# Atmega328p_Shift_Register.net
KiCad netlist of a schematic drawn in EasyEDA Pro
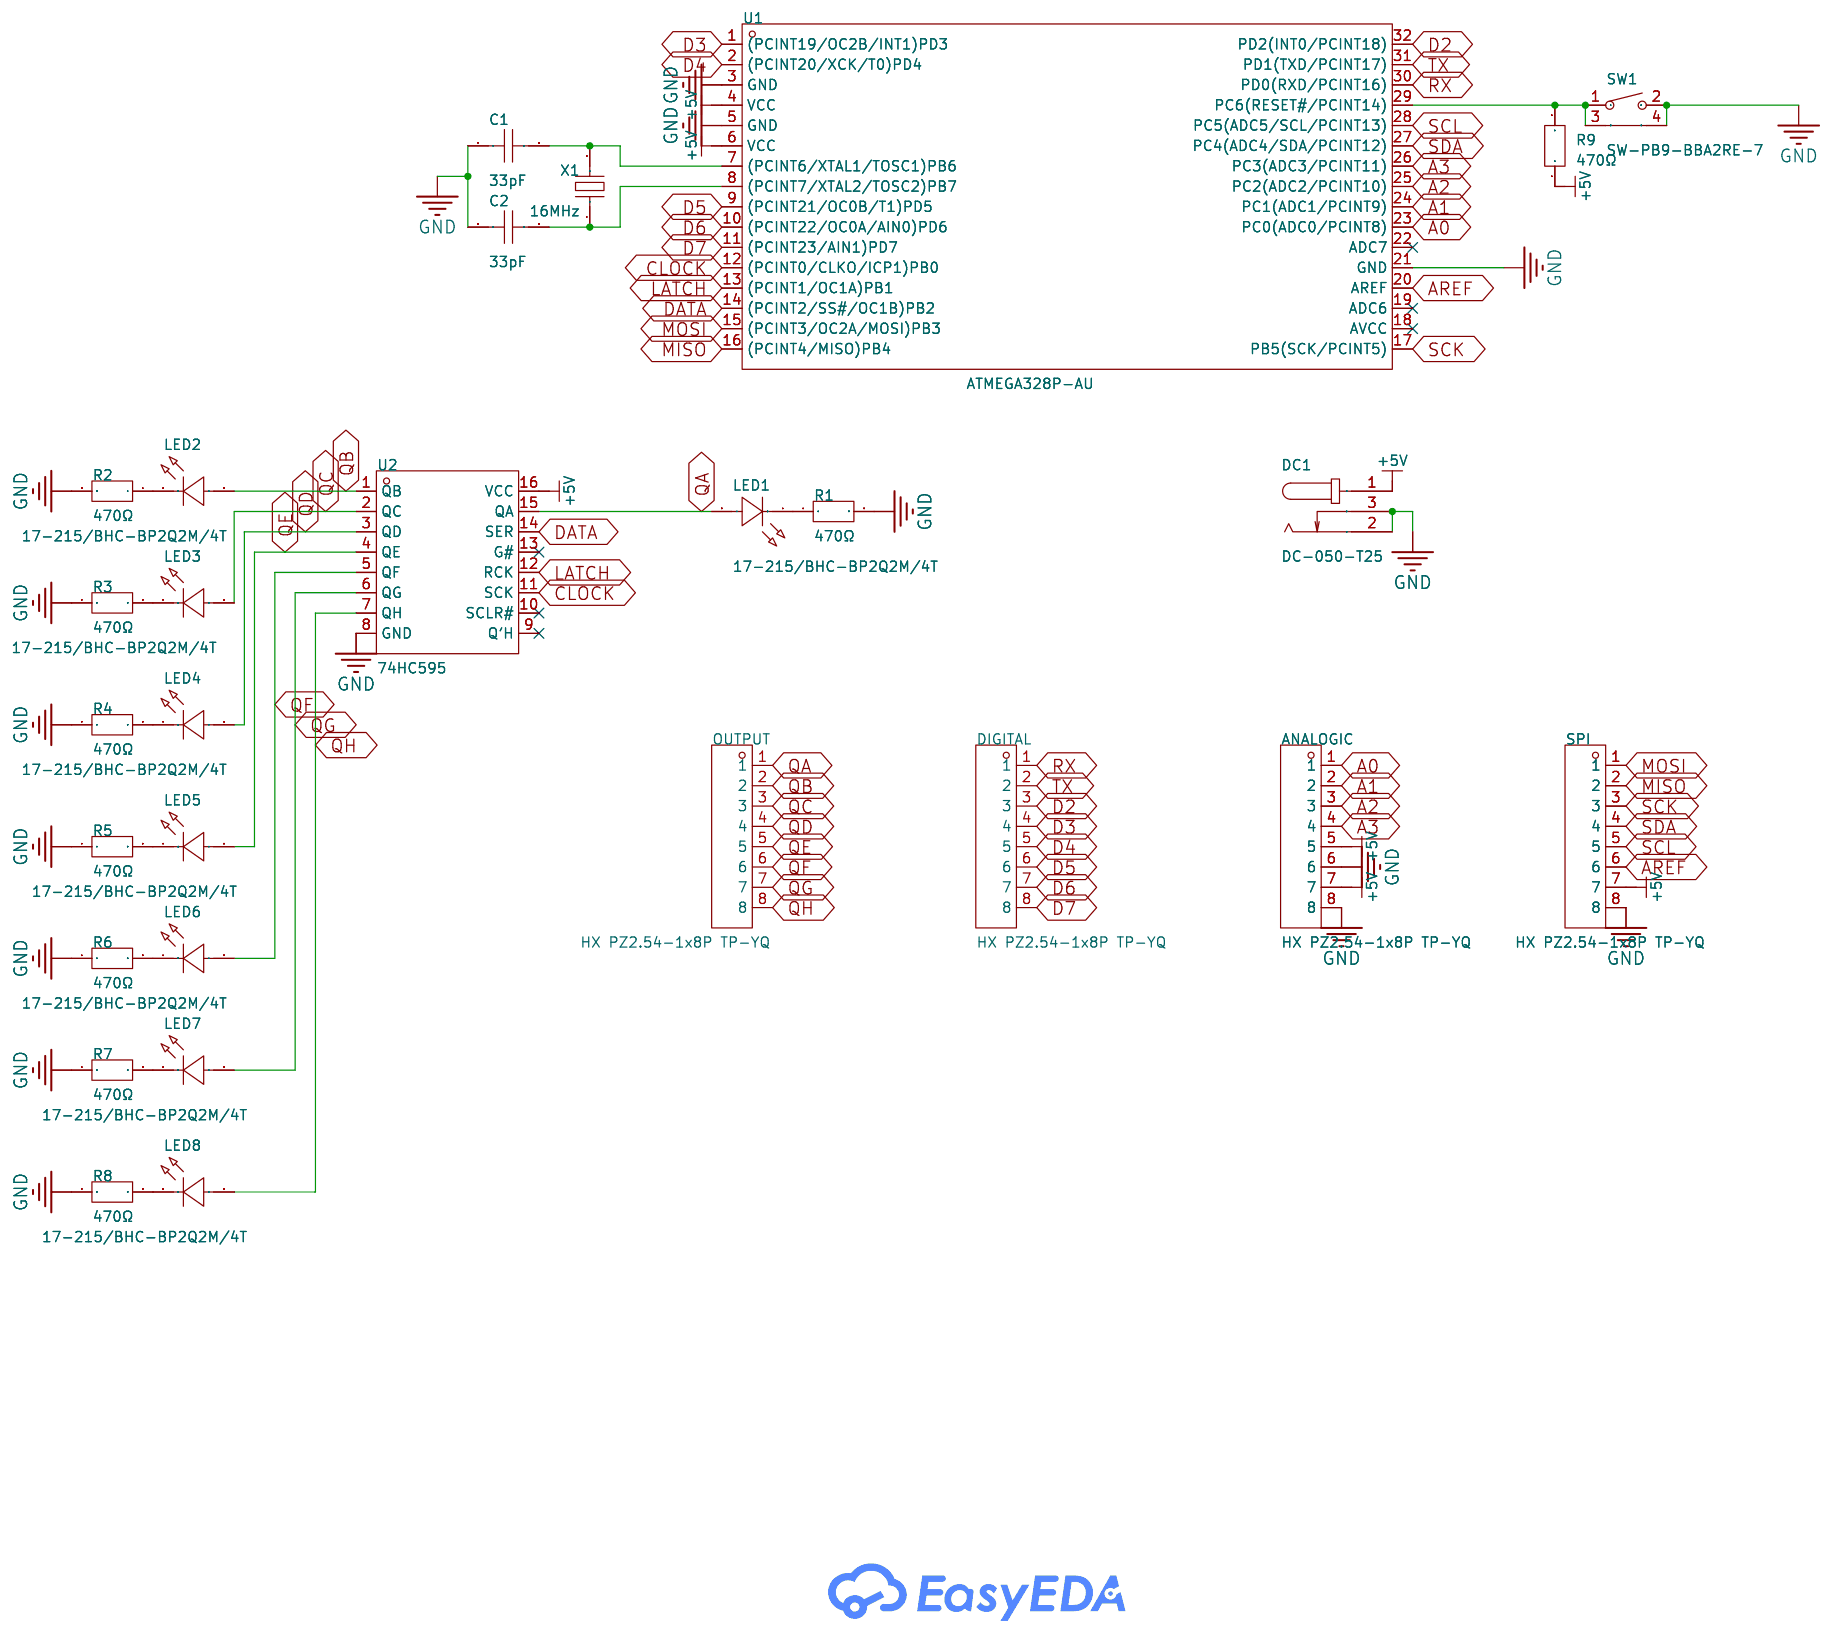
[diagram p0: schematic sheet]

(export (version "E")
  (design (tool "Eeschema 10.0.6"))
  (components
    (comp (ref "ANALOGIC")
      (value "HX PZ2.54-1x8P TP-YQ")
      (footprint "easyedapro:HDR-SMD_8P-P2.54-V-M-LS4.8_XKB_R1")
      (fields (field (name "Manufacturer") "hanxia(韩下)"))
      (libsource (lib "easyedapro") (part "HX PZ2.54-1X8P TP-YQ"))
    )
    (comp (ref "C1")
      (value "33pF")
      (footprint "easyedapro:C0603")
      (fields
        (field (name "Manufacturer Part") "C0603C330J8GAC7867")
        (field (name "Manufacturer") "KEMET(基美)")
      )
      (libsource (lib "easyedapro") (part "C0603C330J8GAC7867"))
    )
    (comp (ref "C2")
      (value "33pF")
      (footprint "easyedapro:C0603")
      (fields
        (field (name "Manufacturer Part") "C0603C330J8GAC7867")
        (field (name "Manufacturer") "KEMET(基美)")
      )
      (libsource (lib "easyedapro") (part "C0603C330J8GAC7867"))
    )
    (comp (ref "DC1")
      (value "DC-050-T25")
      (footprint "easyedapro:DC-IN-SMD_DC-050-T25")
      (fields (field (name "Manufacturer") "SOFNG(硕方)"))
      (libsource (lib "easyedapro") (part "DC-050-T25"))
    )
    (comp (ref "DIGITAL")
      (value "HX PZ2.54-1x8P TP-YQ")
      (footprint "easyedapro:HDR-SMD_8P-P2.54-V-M-LS4.8_XKB_R1")
      (fields (field (name "Manufacturer") "hanxia(韩下)"))
      (libsource (lib "easyedapro") (part "HX PZ2.54-1X8P TP-YQ"))
    )
    (comp (ref "LED1")
      (value "17-215/BHC-BP2Q2M/4T")
      (footprint "easyedapro:LED0805-RD")
      (fields (field (name "Manufacturer") "EVERLIGHT(亿光)"))
      (libsource (lib "easyedapro") (part "17-215/BHC-BP2Q2M/4T"))
    )
    (comp (ref "LED2")
      (value "17-215/BHC-BP2Q2M/4T")
      (footprint "easyedapro:LED0805-RD")
      (fields (field (name "Manufacturer") "EVERLIGHT(亿光)"))
      (libsource (lib "easyedapro") (part "17-215/BHC-BP2Q2M/4T"))
    )
    (comp (ref "LED3")
      (value "17-215/BHC-BP2Q2M/4T")
      (footprint "easyedapro:LED0805-RD")
      (fields (field (name "Manufacturer") "EVERLIGHT(亿光)"))
      (libsource (lib "easyedapro") (part "17-215/BHC-BP2Q2M/4T"))
    )
    (comp (ref "LED4")
      (value "17-215/BHC-BP2Q2M/4T")
      (footprint "easyedapro:LED0805-RD")
      (fields (field (name "Manufacturer") "EVERLIGHT(亿光)"))
      (libsource (lib "easyedapro") (part "17-215/BHC-BP2Q2M/4T"))
    )
    (comp (ref "LED5")
      (value "17-215/BHC-BP2Q2M/4T")
      (footprint "easyedapro:LED0805-RD")
      (fields (field (name "Manufacturer") "EVERLIGHT(亿光)"))
      (libsource (lib "easyedapro") (part "17-215/BHC-BP2Q2M/4T"))
    )
    (comp (ref "LED6")
      (value "17-215/BHC-BP2Q2M/4T")
      (footprint "easyedapro:LED0805-RD")
      (fields (field (name "Manufacturer") "EVERLIGHT(亿光)"))
      (libsource (lib "easyedapro") (part "17-215/BHC-BP2Q2M/4T"))
    )
    (comp (ref "LED7")
      (value "17-215/BHC-BP2Q2M/4T")
      (footprint "easyedapro:LED0805-RD")
      (fields (field (name "Manufacturer") "EVERLIGHT(亿光)"))
      (libsource (lib "easyedapro") (part "17-215/BHC-BP2Q2M/4T"))
    )
    (comp (ref "LED8")
      (value "17-215/BHC-BP2Q2M/4T")
      (footprint "easyedapro:LED0805-RD")
      (fields (field (name "Manufacturer") "EVERLIGHT(亿光)"))
      (libsource (lib "easyedapro") (part "17-215/BHC-BP2Q2M/4T"))
    )
    (comp (ref "OUTPUT")
      (value "HX PZ2.54-1x8P TP-YQ")
      (footprint "easyedapro:HDR-SMD_8P-P2.54-V-M-LS4.8_XKB_R1")
      (fields (field (name "Manufacturer") "hanxia(韩下)"))
      (libsource (lib "easyedapro") (part "HX PZ2.54-1X8P TP-YQ"))
    )
    (comp (ref "R1")
      (value "470Ω")
      (footprint "easyedapro:R0805")
      (fields (field (name "Manufacturer Part") "RC2012F471CS") (field (name "Manufacturer") "SAMSUNG(三星)"))
      (libsource (lib "easyedapro") (part "RC2012F471CS"))
    )
    (comp (ref "R2")
      (value "470Ω")
      (footprint "easyedapro:R0805")
      (fields (field (name "Manufacturer Part") "RC2012F471CS") (field (name "Manufacturer") "SAMSUNG(三星)"))
      (libsource (lib "easyedapro") (part "RC2012F471CS"))
    )
    (comp (ref "R3")
      (value "470Ω")
      (footprint "easyedapro:R0805")
      (fields (field (name "Manufacturer Part") "RC2012F471CS") (field (name "Manufacturer") "SAMSUNG(三星)"))
      (libsource (lib "easyedapro") (part "RC2012F471CS"))
    )
    (comp (ref "R4")
      (value "470Ω")
      (footprint "easyedapro:R0805")
      (fields (field (name "Manufacturer Part") "RC2012F471CS") (field (name "Manufacturer") "SAMSUNG(三星)"))
      (libsource (lib "easyedapro") (part "RC2012F471CS"))
    )
    (comp (ref "R5")
      (value "470Ω")
      (footprint "easyedapro:R0805")
      (fields (field (name "Manufacturer Part") "RC2012F471CS") (field (name "Manufacturer") "SAMSUNG(三星)"))
      (libsource (lib "easyedapro") (part "RC2012F471CS"))
    )
    (comp (ref "R6")
      (value "470Ω")
      (footprint "easyedapro:R0805")
      (fields (field (name "Manufacturer Part") "RC2012F471CS") (field (name "Manufacturer") "SAMSUNG(三星)"))
      (libsource (lib "easyedapro") (part "RC2012F471CS"))
    )
    (comp (ref "R7")
      (value "470Ω")
      (footprint "easyedapro:R0805")
      (fields (field (name "Manufacturer Part") "RC2012F471CS") (field (name "Manufacturer") "SAMSUNG(三星)"))
      (libsource (lib "easyedapro") (part "RC2012F471CS"))
    )
    (comp (ref "R8")
      (value "470Ω")
      (footprint "easyedapro:R0805")
      (fields (field (name "Manufacturer Part") "RC2012F471CS") (field (name "Manufacturer") "SAMSUNG(三星)"))
      (libsource (lib "easyedapro") (part "RC2012F471CS"))
    )
    (comp (ref "R9")
      (value "470Ω")
      (footprint "easyedapro:R0805")
      (fields (field (name "Manufacturer Part") "RC2012F471CS") (field (name "Manufacturer") "SAMSUNG(三星)"))
      (libsource (lib "easyedapro") (part "RC2012F471CS"))
    )
    (comp (ref "SPI")
      (value "HX PZ2.54-1x8P TP-YQ")
      (footprint "easyedapro:HDR-SMD_8P-P2.54-V-M-LS4.8_XKB_R1")
      (fields (field (name "Manufacturer") "hanxia(韩下)"))
      (libsource (lib "easyedapro") (part "HX PZ2.54-1X8P TP-YQ"))
    )
    (comp (ref "SW1")
      (value "SW-PB9-BBA2RE-7")
      (footprint "easyedapro:SW-SMD_SW-PB9-BBA2RE-7")
      (fields (field (name "Manufacturer") "ADAM TECH"))
      (libsource (lib "easyedapro") (part "SW-PB9-BBA2RE-7"))
    )
    (comp (ref "U1")
      (value "ATMEGA328P-AU")
      (footprint "easyedapro:TQFP-32_L7.0-W7.0-P0.80-LS9.0-BL")
      (fields (field (name "Manufacturer") "MICROCHIP(美国微芯)"))
      (libsource (lib "easyedapro") (part "ATMEGA328P-AU"))
    )
    (comp (ref "U2")
      (value "74HC595")
      (footprint "easyedapro:SOP-16_L9.9-W3.9-P1.27-LS6.0-BL")
      (fields (field (name "Manufacturer") "GR(国睿)"))
      (libsource (lib "easyedapro") (part "74HC595"))
    )
    (comp (ref "X1")
      (value "16MHz")
      (footprint "easyedapro:HC-49S_L7.0-W4.0-LS8.0")
      (fields
        (field (name "Manufacturer Part") "S47SMD16.000M20PF30R30B3")
        (field (name "Manufacturer") "SST(索斯特)")
      )
      (libsource (lib "easyedapro") (part "S47SMD16.000M20PF30R30B3"))
    )
  )
  (nets
    (net (code "1") (name "+5V") (class "Default")
      (node (ref "ANALOGIC") (pin "5") (pinfunction "5_5") (pintype "unspecified"))
      (node (ref "ANALOGIC") (pin "7") (pinfunction "7_7") (pintype "unspecified"))
      (node (ref "DC1") (pin "1") (pinfunction "1_1") (pintype "unspecified"))
      (node (ref "R9") (pin "1") (pinfunction "1_1") (pintype "unspecified"))
      (node (ref "SPI") (pin "7") (pinfunction "7_7") (pintype "unspecified"))
      (node (ref "U1") (pin "4") (pinfunction "VCC_4") (pintype "unspecified"))
      (node (ref "U1") (pin "6") (pinfunction "VCC_6") (pintype "unspecified"))
      (node (ref "U2") (pin "16") (pinfunction "VCC_16") (pintype "unspecified"))
    )
    (net (code "2") (name "A0") (class "Default")
      (node (ref "ANALOGIC") (pin "1") (pinfunction "1_1") (pintype "unspecified"))
      (node (ref "U1") (pin "23") (pinfunction "PC0(ADC0/PCINT8)_23") (pintype "unspecified"))
    )
    (net (code "3") (name "A1") (class "Default")
      (node (ref "ANALOGIC") (pin "2") (pinfunction "2_2") (pintype "unspecified"))
      (node (ref "U1") (pin "24") (pinfunction "PC1(ADC1/PCINT9)_24") (pintype "unspecified"))
    )
    (net (code "4") (name "A2") (class "Default")
      (node (ref "ANALOGIC") (pin "3") (pinfunction "3_3") (pintype "unspecified"))
      (node (ref "U1") (pin "25") (pinfunction "PC2(ADC2/PCINT10)_25") (pintype "unspecified"))
    )
    (net (code "5") (name "A3") (class "Default")
      (node (ref "ANALOGIC") (pin "4") (pinfunction "4_4") (pintype "unspecified"))
      (node (ref "U1") (pin "26") (pinfunction "PC3(ADC3/PCINT11)_26") (pintype "unspecified"))
    )
    (net (code "6") (name "AREF") (class "Default")
      (node (ref "SPI") (pin "6") (pinfunction "6_6") (pintype "unspecified"))
      (node (ref "U1") (pin "20") (pinfunction "AREF_20") (pintype "unspecified"))
    )
    (net (code "7") (name "CLOCK") (class "Default")
      (node (ref "U1") (pin "12") (pinfunction "(PCINT0/CLKO/ICP1)PB0_12") (pintype "unspecified"))
      (node (ref "U2") (pin "11") (pinfunction "SCK_11") (pintype "unspecified"))
    )
    (net (code "8") (name "D2") (class "Default")
      (node (ref "DIGITAL") (pin "3") (pinfunction "3_3") (pintype "unspecified"))
      (node (ref "U1") (pin "32") (pinfunction "PD2(INT0/PCINT18)_32") (pintype "unspecified"))
    )
    (net (code "9") (name "D3") (class "Default")
      (node (ref "DIGITAL") (pin "4") (pinfunction "4_4") (pintype "unspecified"))
      (node (ref "U1") (pin "1") (pinfunction "(PCINT19/OC2B/INT1)PD3_1") (pintype "unspecified"))
    )
    (net (code "10") (name "D4") (class "Default")
      (node (ref "DIGITAL") (pin "5") (pinfunction "5_5") (pintype "unspecified"))
      (node (ref "U1") (pin "2") (pinfunction "(PCINT20/XCK/T0)PD4_2") (pintype "unspecified"))
    )
    (net (code "11") (name "D5") (class "Default")
      (node (ref "DIGITAL") (pin "6") (pinfunction "6_6") (pintype "unspecified"))
      (node (ref "U1") (pin "9") (pinfunction "(PCINT21/OC0B/T1)PD5_9") (pintype "unspecified"))
    )
    (net (code "12") (name "D6") (class "Default")
      (node (ref "DIGITAL") (pin "7") (pinfunction "7_7") (pintype "unspecified"))
      (node (ref "U1") (pin "10") (pinfunction "(PCINT22/OC0A/AIN0)PD6_10") (pintype "unspecified"))
    )
    (net (code "13") (name "D7") (class "Default")
      (node (ref "DIGITAL") (pin "8") (pinfunction "8_8") (pintype "unspecified"))
      (node (ref "U1") (pin "11") (pinfunction "(PCINT23/AIN1)PD7_11") (pintype "unspecified"))
    )
    (net (code "14") (name "DATA") (class "Default")
      (node (ref "U1") (pin "14") (pinfunction "(PCINT2/SS#/OC1B)PB2_14") (pintype "unspecified"))
      (node (ref "U2") (pin "14") (pinfunction "SER_14") (pintype "unspecified"))
    )
    (net (code "15") (name "GND") (class "Default")
      (node (ref "ANALOGIC") (pin "6") (pinfunction "6_6") (pintype "unspecified"))
      (node (ref "ANALOGIC") (pin "8") (pinfunction "8_8") (pintype "unspecified"))
      (node (ref "C1") (pin "1") (pinfunction "1_1") (pintype "unspecified"))
      (node (ref "C2") (pin "1") (pinfunction "1_1") (pintype "unspecified"))
      (node (ref "DC1") (pin "2") (pinfunction "2_2") (pintype "unspecified"))
      (node (ref "DC1") (pin "3") (pinfunction "3_3") (pintype "unspecified"))
      (node (ref "R1") (pin "2") (pinfunction "2_2") (pintype "unspecified"))
      (node (ref "R2") (pin "2") (pinfunction "2_2") (pintype "unspecified"))
      (node (ref "R3") (pin "1") (pinfunction "1_1") (pintype "unspecified"))
      (node (ref "R4") (pin "1") (pinfunction "1_1") (pintype "unspecified"))
      (node (ref "R5") (pin "1") (pinfunction "1_1") (pintype "unspecified"))
      (node (ref "R6") (pin "1") (pinfunction "1_1") (pintype "unspecified"))
      (node (ref "R7") (pin "1") (pinfunction "1_1") (pintype "unspecified"))
      (node (ref "R8") (pin "1") (pinfunction "1_1") (pintype "unspecified"))
      (node (ref "SPI") (pin "8") (pinfunction "8_8") (pintype "unspecified"))
      (node (ref "SW1") (pin "2") (pinfunction "2_2") (pintype "unspecified"))
      (node (ref "SW1") (pin "4") (pinfunction "EP_4") (pintype "unspecified"))
      (node (ref "U1") (pin "21") (pinfunction "GND_21") (pintype "unspecified"))
      (node (ref "U1") (pin "3") (pinfunction "GND_3") (pintype "unspecified"))
      (node (ref "U1") (pin "5") (pinfunction "GND_5") (pintype "unspecified"))
      (node (ref "U2") (pin "8") (pinfunction "GND_8") (pintype "unspecified"))
    )
    (net (code "16") (name "LATCH") (class "Default")
      (node (ref "U1") (pin "13") (pinfunction "(PCINT1/OC1A)PB1_13") (pintype "unspecified"))
      (node (ref "U2") (pin "12") (pinfunction "RCK_12") (pintype "unspecified"))
    )
    (net (code "17") (name "MISO") (class "Default")
      (node (ref "SPI") (pin "2") (pinfunction "2_2") (pintype "unspecified"))
      (node (ref "U1") (pin "16") (pinfunction "(PCINT4/MISO)PB4_16") (pintype "unspecified"))
    )
    (net (code "18") (name "MOSI") (class "Default")
      (node (ref "SPI") (pin "1") (pinfunction "1_1") (pintype "unspecified"))
      (node (ref "U1") (pin "15") (pinfunction "(PCINT3/OC2A/MOSI)PB3_15") (pintype "unspecified"))
    )
    (net (code "19") (name "Net-(LED1-C)") (class "Default")
      (node (ref "LED1") (pin "1") (pinfunction "C_1") (pintype "unspecified"))
      (node (ref "R1") (pin "1") (pinfunction "1_1") (pintype "unspecified"))
    )
    (net (code "20") (name "Net-(LED2-C)") (class "Default")
      (node (ref "LED2") (pin "1") (pinfunction "C_1") (pintype "unspecified"))
      (node (ref "R2") (pin "1") (pinfunction "1_1") (pintype "unspecified"))
    )
    (net (code "21") (name "Net-(LED3-C)") (class "Default")
      (node (ref "LED3") (pin "1") (pinfunction "C_1") (pintype "unspecified"))
      (node (ref "R3") (pin "2") (pinfunction "2_2") (pintype "unspecified"))
    )
    (net (code "22") (name "Net-(LED4-C)") (class "Default")
      (node (ref "LED4") (pin "1") (pinfunction "C_1") (pintype "unspecified"))
      (node (ref "R4") (pin "2") (pinfunction "2_2") (pintype "unspecified"))
    )
    (net (code "23") (name "Net-(LED5-C)") (class "Default")
      (node (ref "LED5") (pin "1") (pinfunction "C_1") (pintype "unspecified"))
      (node (ref "R5") (pin "2") (pinfunction "2_2") (pintype "unspecified"))
    )
    (net (code "24") (name "Net-(LED6-C)") (class "Default")
      (node (ref "LED6") (pin "1") (pinfunction "C_1") (pintype "unspecified"))
      (node (ref "R6") (pin "2") (pinfunction "2_2") (pintype "unspecified"))
    )
    (net (code "25") (name "Net-(LED7-C)") (class "Default")
      (node (ref "LED7") (pin "1") (pinfunction "C_1") (pintype "unspecified"))
      (node (ref "R7") (pin "2") (pinfunction "2_2") (pintype "unspecified"))
    )
    (net (code "26") (name "Net-(LED8-C)") (class "Default")
      (node (ref "LED8") (pin "1") (pinfunction "C_1") (pintype "unspecified"))
      (node (ref "R8") (pin "2") (pinfunction "2_2") (pintype "unspecified"))
    )
    (net (code "27") (name "Net-(U1-(PCINT6{slash}XTAL1{slash}TOSC1)PB6)") (class "Default")
      (node (ref "C1") (pin "2") (pinfunction "2_2") (pintype "unspecified"))
      (node (ref "U1") (pin "7") (pinfunction "(PCINT6/XTAL1/TOSC1)PB6_7") (pintype "unspecified"))
      (node (ref "X1") (pin "2") (pinfunction "2_2") (pintype "input"))
    )
    (net (code "28") (name "Net-(U1-(PCINT7{slash}XTAL2{slash}TOSC2)PB7)") (class "Default")
      (node (ref "C2") (pin "2") (pinfunction "2_2") (pintype "unspecified"))
      (node (ref "U1") (pin "8") (pinfunction "(PCINT7/XTAL2/TOSC2)PB7_8") (pintype "unspecified"))
      (node (ref "X1") (pin "1") (pinfunction "1_1") (pintype "input"))
    )
    (net (code "29") (name "Net-(U1-PC6(RESET#{slash}PCINT14))") (class "Default")
      (node (ref "R9") (pin "2") (pinfunction "2_2") (pintype "unspecified"))
      (node (ref "SW1") (pin "1") (pinfunction "1_1") (pintype "unspecified"))
      (node (ref "SW1") (pin "3") (pinfunction "EP_3") (pintype "unspecified"))
      (node (ref "U1") (pin "29") (pinfunction "PC6(RESET#/PCINT14)_29") (pintype "unspecified"))
    )
    (net (code "30") (name "QA") (class "Default")
      (node (ref "LED1") (pin "2") (pinfunction "A_2") (pintype "unspecified"))
      (node (ref "OUTPUT") (pin "1") (pinfunction "1_1") (pintype "unspecified"))
      (node (ref "U2") (pin "15") (pinfunction "QA_15") (pintype "unspecified"))
    )
    (net (code "31") (name "QB") (class "Default")
      (node (ref "LED2") (pin "2") (pinfunction "A_2") (pintype "unspecified"))
      (node (ref "OUTPUT") (pin "2") (pinfunction "2_2") (pintype "unspecified"))
      (node (ref "U2") (pin "1") (pinfunction "QB_1") (pintype "unspecified"))
    )
    (net (code "32") (name "QC") (class "Default")
      (node (ref "LED3") (pin "2") (pinfunction "A_2") (pintype "unspecified"))
      (node (ref "OUTPUT") (pin "3") (pinfunction "3_3") (pintype "unspecified"))
      (node (ref "U2") (pin "2") (pinfunction "QC_2") (pintype "unspecified"))
    )
    (net (code "33") (name "QD") (class "Default")
      (node (ref "LED4") (pin "2") (pinfunction "A_2") (pintype "unspecified"))
      (node (ref "OUTPUT") (pin "4") (pinfunction "4_4") (pintype "unspecified"))
      (node (ref "U2") (pin "3") (pinfunction "QD_3") (pintype "unspecified"))
    )
    (net (code "34") (name "QE") (class "Default")
      (node (ref "LED5") (pin "2") (pinfunction "A_2") (pintype "unspecified"))
      (node (ref "OUTPUT") (pin "5") (pinfunction "5_5") (pintype "unspecified"))
      (node (ref "U2") (pin "4") (pinfunction "QE_4") (pintype "unspecified"))
    )
    (net (code "35") (name "QF") (class "Default")
      (node (ref "LED6") (pin "2") (pinfunction "A_2") (pintype "unspecified"))
      (node (ref "OUTPUT") (pin "6") (pinfunction "6_6") (pintype "unspecified"))
      (node (ref "U2") (pin "5") (pinfunction "QF_5") (pintype "unspecified"))
    )
    (net (code "36") (name "QG") (class "Default")
      (node (ref "LED7") (pin "2") (pinfunction "A_2") (pintype "unspecified"))
      (node (ref "OUTPUT") (pin "7") (pinfunction "7_7") (pintype "unspecified"))
      (node (ref "U2") (pin "6") (pinfunction "QG_6") (pintype "unspecified"))
    )
    (net (code "37") (name "QH") (class "Default")
      (node (ref "LED8") (pin "2") (pinfunction "A_2") (pintype "unspecified"))
      (node (ref "OUTPUT") (pin "8") (pinfunction "8_8") (pintype "unspecified"))
      (node (ref "U2") (pin "7") (pinfunction "QH_7") (pintype "unspecified"))
    )
    (net (code "38") (name "RX") (class "Default")
      (node (ref "DIGITAL") (pin "1") (pinfunction "1_1") (pintype "unspecified"))
      (node (ref "U1") (pin "30") (pinfunction "PD0(RXD/PCINT16)_30") (pintype "unspecified"))
    )
    (net (code "39") (name "SCK") (class "Default")
      (node (ref "SPI") (pin "3") (pinfunction "3_3") (pintype "unspecified"))
      (node (ref "U1") (pin "17") (pinfunction "PB5(SCK/PCINT5)_17") (pintype "unspecified"))
    )
    (net (code "40") (name "SCL") (class "Default")
      (node (ref "SPI") (pin "5") (pinfunction "5_5") (pintype "unspecified"))
      (node (ref "U1") (pin "28") (pinfunction "PC5(ADC5/SCL/PCINT13)_28") (pintype "unspecified"))
    )
    (net (code "41") (name "SDA") (class "Default")
      (node (ref "SPI") (pin "4") (pinfunction "4_4") (pintype "unspecified"))
      (node (ref "U1") (pin "27") (pinfunction "PC4(ADC4/SDA/PCINT12)_27") (pintype "unspecified"))
    )
    (net (code "42") (name "TX") (class "Default")
      (node (ref "DIGITAL") (pin "2") (pinfunction "2_2") (pintype "unspecified"))
      (node (ref "U1") (pin "31") (pinfunction "PD1(TXD/PCINT17)_31") (pintype "unspecified"))
    )
    (net (code "43") (name "unconnected-(U1-ADC6-Pad19)") (class "Default")
      (node (ref "U1") (pin "19") (pinfunction "ADC6_19") (pintype "unspecified+no_connect"))
    )
    (net (code "44") (name "unconnected-(U1-ADC7-Pad22)") (class "Default")
      (node (ref "U1") (pin "22") (pinfunction "ADC7_22") (pintype "unspecified+no_connect"))
    )
    (net (code "45") (name "unconnected-(U1-AVCC-Pad18)") (class "Default")
      (node (ref "U1") (pin "18") (pinfunction "AVCC_18") (pintype "unspecified+no_connect"))
    )
    (net (code "46") (name "unconnected-(U2-G#-Pad13)") (class "Default")
      (node (ref "U2") (pin "13") (pinfunction "G#_13") (pintype "unspecified+no_connect"))
    )
    (net (code "47") (name "unconnected-(U2-Q′H-Pad9)") (class "Default")
      (node (ref "U2") (pin "9") (pinfunction "Q′H_9") (pintype "unspecified+no_connect"))
    )
    (net (code "48") (name "unconnected-(U2-SCLR#-Pad10)") (class "Default")
      (node (ref "U2") (pin "10") (pinfunction "SCLR#_10") (pintype "unspecified+no_connect"))
    )
  )
)
